# WaterMonitorV5_0.net
KiCad netlist of a schematic drawn in EAGLE
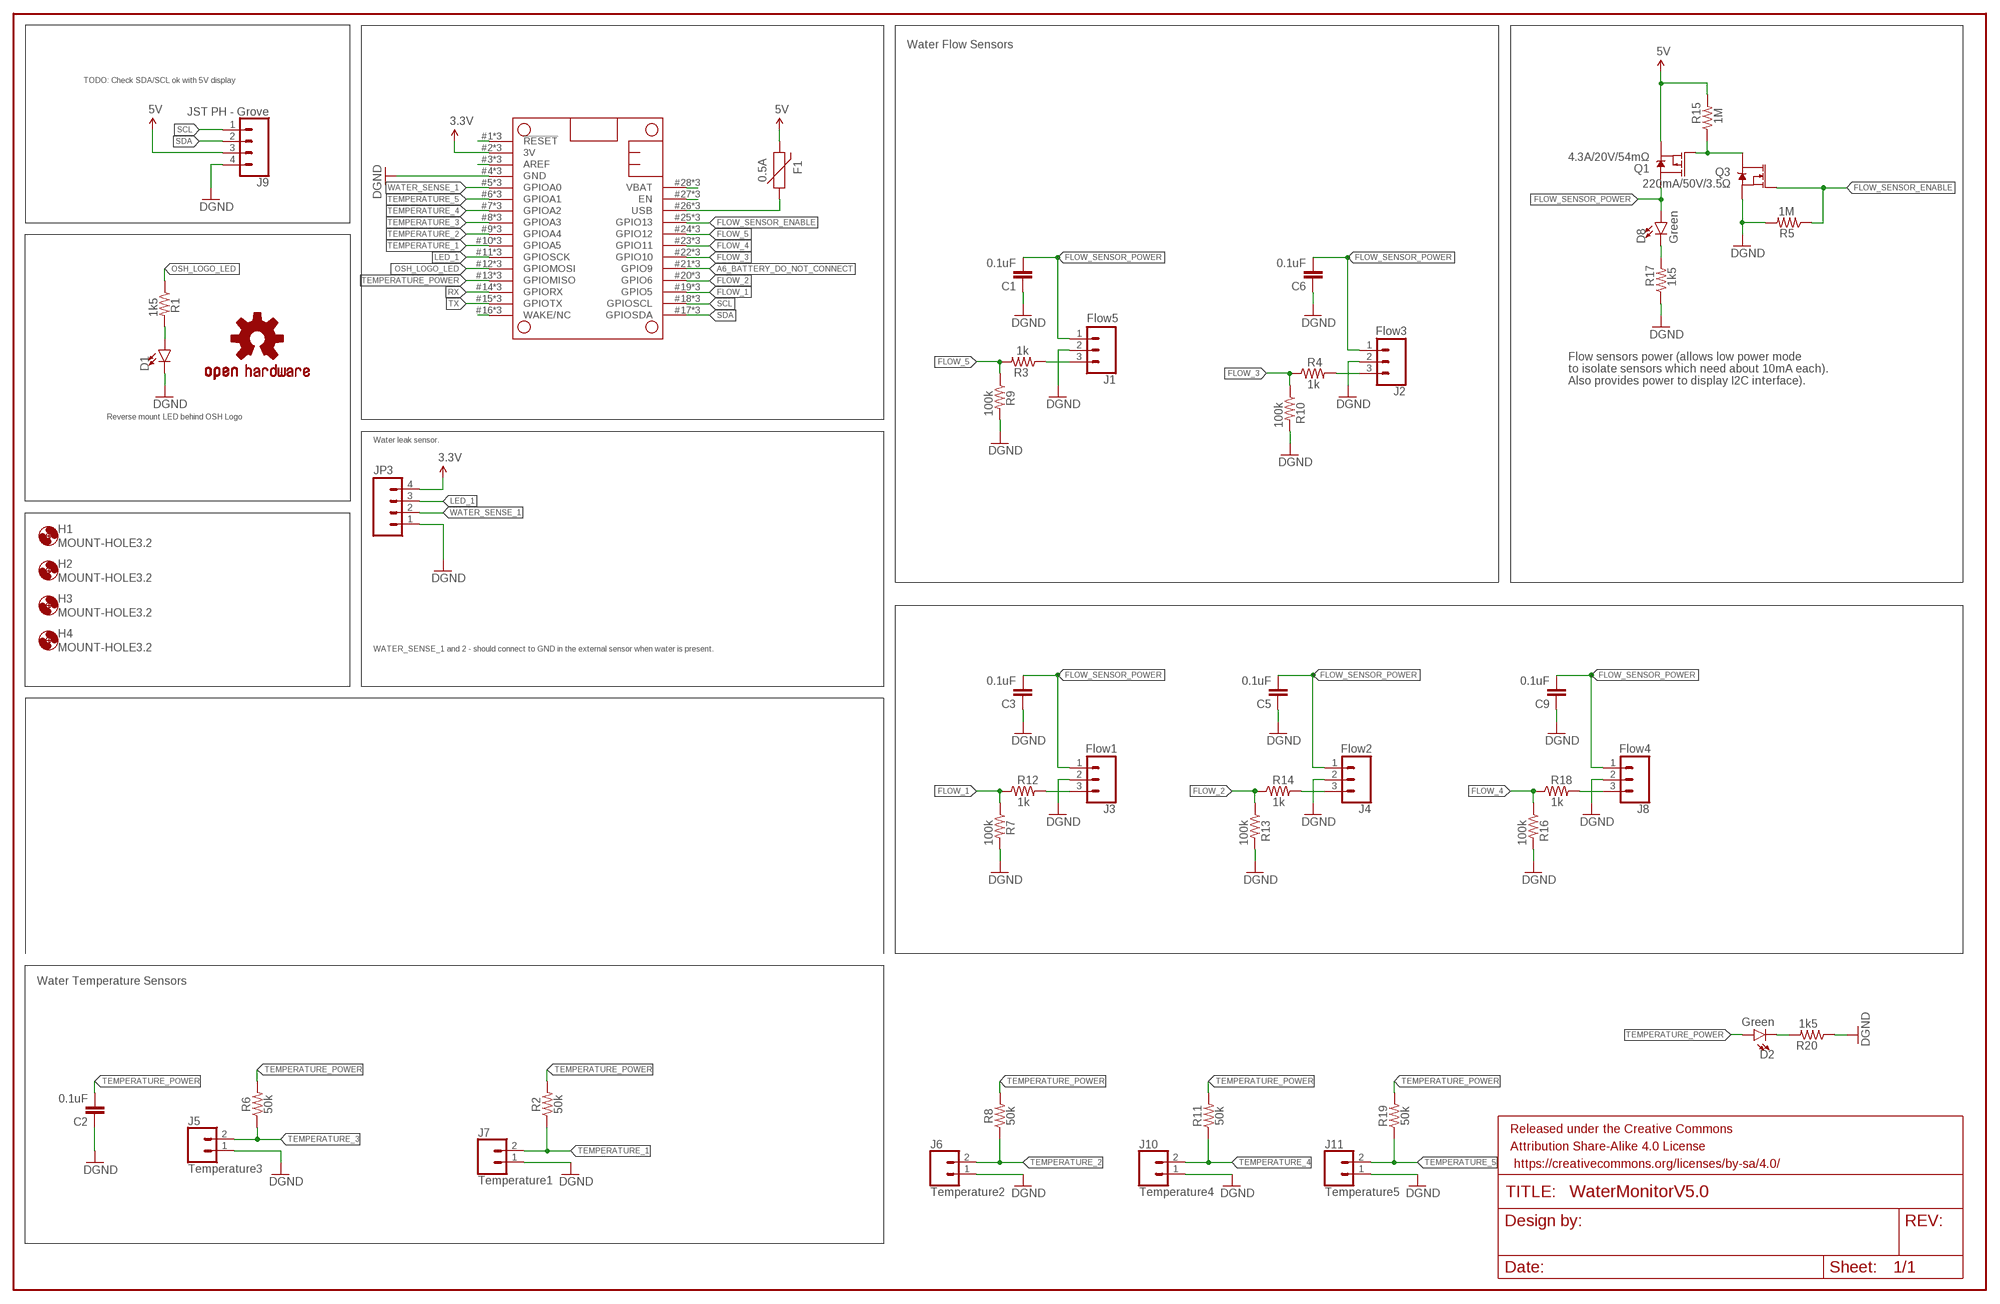
[diagram p0: schematic, sheet 1]

(export (version "E")
  (design (tool "Eeschema 10.0.6"))
  (components
    (comp (ref "C1")
      (value "0.1uF")
      (footprint "eagle-import:0805")
      (libsource (lib "eagle-import") (part "CAP0805"))
    )
    (comp (ref "C2")
      (value "0.1uF")
      (footprint "eagle-import:0805")
      (libsource (lib "eagle-import") (part "CAP0805"))
    )
    (comp (ref "C3")
      (value "0.1uF")
      (footprint "eagle-import:0805")
      (libsource (lib "eagle-import") (part "CAP0805"))
    )
    (comp (ref "C5")
      (value "0.1uF")
      (footprint "eagle-import:0805")
      (libsource (lib "eagle-import") (part "CAP0805"))
    )
    (comp (ref "C6")
      (value "0.1uF")
      (footprint "eagle-import:0805")
      (libsource (lib "eagle-import") (part "CAP0805"))
    )
    (comp (ref "C9")
      (value "0.1uF")
      (footprint "eagle-import:0805")
      (libsource (lib "eagle-import") (part "CAP0805"))
    )
    (comp (ref "D1")
      (value "LED1206-BOTTOM")
      (footprint "eagle-import:LED-1206-BOTTOM")
      (libsource (lib "eagle-import") (part "LED1206-BOTTOM"))
    )
    (comp (ref "D2")
      (value "Green")
      (footprint "eagle-import:LED-1206")
      (libsource (lib "eagle-import") (part "LED-BLUE1206"))
    )
    (comp (ref "D8")
      (value "Green")
      (footprint "eagle-import:LED-1206")
      (libsource (lib "eagle-import") (part "LED-BLUE1206"))
    )
    (comp (ref "F1")
      (value "0.5A")
      (footprint "eagle-import:1206")
      (libsource (lib "eagle-import") (part "PPTC_HALF-AMP"))
    )
    (comp (ref "FRAME2")
      (value "FRAME-LEDGER")
      (footprint "eagle-import:CREATIVE_COMMONS")
      (libsource (lib "eagle-import") (part "FRAME-LEDGER"))
    )
    (comp (ref "H1")
      (value "MOUNT-HOLE3.2")
      (footprint "eagle-import:3,2")
      (libsource (lib "eagle-import") (part "MOUNT-HOLE3.2"))
    )
    (comp (ref "H2")
      (value "MOUNT-HOLE3.2")
      (footprint "eagle-import:3,2")
      (libsource (lib "eagle-import") (part "MOUNT-HOLE3.2"))
    )
    (comp (ref "H3")
      (value "MOUNT-HOLE3.2")
      (footprint "eagle-import:3,2")
      (libsource (lib "eagle-import") (part "MOUNT-HOLE3.2"))
    )
    (comp (ref "H4")
      (value "MOUNT-HOLE3.2")
      (footprint "eagle-import:3,2")
      (libsource (lib "eagle-import") (part "MOUNT-HOLE3.2"))
    )
    (comp (ref "J1")
      (value "Flow5")
      (footprint "eagle-import:JST-HX-3-PTH-VERT")
      (libsource (lib "eagle-import") (part "CONN_03JST-HX-PTH-VERT"))
    )
    (comp (ref "J2")
      (value "Flow3")
      (footprint "eagle-import:JST-HX-3-PTH-VERT")
      (libsource (lib "eagle-import") (part "CONN_03JST-HX-PTH-VERT"))
    )
    (comp (ref "J3")
      (value "Flow1")
      (footprint "eagle-import:JST-HX-3-PTH-VERT")
      (libsource (lib "eagle-import") (part "CONN_03JST-HX-PTH-VERT"))
    )
    (comp (ref "J4")
      (value "Flow2")
      (footprint "eagle-import:JST-HX-3-PTH-VERT")
      (libsource (lib "eagle-import") (part "CONN_03JST-HX-PTH-VERT"))
    )
    (comp (ref "J5")
      (value "Temperature3")
      (footprint "eagle-import:MOLEX-1X2")
      (libsource (lib "eagle-import") (part "CONN_02POLAR"))
    )
    (comp (ref "J6")
      (value "Temperature2")
      (footprint "eagle-import:MOLEX-1X2")
      (libsource (lib "eagle-import") (part "CONN_02POLAR"))
    )
    (comp (ref "J7")
      (value "Temperature1")
      (footprint "eagle-import:MOLEX-1X2")
      (libsource (lib "eagle-import") (part "CONN_02POLAR"))
    )
    (comp (ref "J8")
      (value "Flow4")
      (footprint "eagle-import:JST-HX-3-PTH-VERT")
      (libsource (lib "eagle-import") (part "CONN_03JST-HX-PTH-VERT"))
    )
    (comp (ref "J9")
      (value "JST PH - Grove")
      (footprint "eagle-import:JST-4-PTH-VERT")
      (libsource (lib "eagle-import") (part "CONN_04JST-PTH-VERT"))
    )
    (comp (ref "J10")
      (value "Temperature4")
      (footprint "eagle-import:MOLEX-1X2")
      (libsource (lib "eagle-import") (part "CONN_02POLAR"))
    )
    (comp (ref "J11")
      (value "Temperature5")
      (footprint "eagle-import:MOLEX-1X2")
      (libsource (lib "eagle-import") (part "CONN_02POLAR"))
    )
    (comp (ref "JP3")
      (value "M04POLAR")
      (footprint "eagle-import:MOLEX-1X4@1")
      (libsource (lib "eagle-import") (part "M04POLAR"))
    )
    (comp (ref "LOGO1")
      (value "OSHW-LOGOM")
      (footprint "eagle-import:OSHW-LOGO-M")
      (libsource (lib "eagle-import") (part "OSHW-LOGOM"))
    )
    (comp (ref "MS1")
      (value "FEATHERWINGFEATHEWING_BREAKOUT")
      (footprint "eagle-import:FEATHERWING_BREAKOUT")
      (libsource (lib "eagle-import") (part "FEATHERWINGFEATHEWING_BREAKOUT"))
    )
    (comp (ref "Q1")
      (value "4.3A/20V/54mΩ")
      (footprint "eagle-import:SOT23-3")
      (libsource (lib "eagle-import") (part "MOSFET_PCH-IRLML2244"))
    )
    (comp (ref "Q3")
      (value "220mA/50V/3.5Ω")
      (footprint "eagle-import:SOT23-3")
      (libsource (lib "eagle-import") (part "MOSFET-NCH-BSS138"))
    )
    (comp (ref "R1")
      (value "1k5")
      (footprint "eagle-import:0805")
      (libsource (lib "eagle-import") (part "RESISTOR0805"))
    )
    (comp (ref "R2")
      (value "50k")
      (footprint "eagle-import:0805")
      (libsource (lib "eagle-import") (part "RESISTOR0805"))
    )
    (comp (ref "R3")
      (value "1k")
      (footprint "eagle-import:0805")
      (libsource (lib "eagle-import") (part "RESISTOR0805"))
    )
    (comp (ref "R4")
      (value "1k")
      (footprint "eagle-import:0805")
      (libsource (lib "eagle-import") (part "RESISTOR0805"))
    )
    (comp (ref "R5")
      (value "1M")
      (footprint "eagle-import:0805")
      (libsource (lib "eagle-import") (part "RESISTOR0805"))
    )
    (comp (ref "R6")
      (value "50k")
      (footprint "eagle-import:0805")
      (libsource (lib "eagle-import") (part "RESISTOR0805"))
    )
    (comp (ref "R7")
      (value "100k")
      (footprint "eagle-import:0805")
      (libsource (lib "eagle-import") (part "RESISTOR0805"))
    )
    (comp (ref "R8")
      (value "50k")
      (footprint "eagle-import:0805")
      (libsource (lib "eagle-import") (part "RESISTOR0805"))
    )
    (comp (ref "R9")
      (value "100k")
      (footprint "eagle-import:0805")
      (libsource (lib "eagle-import") (part "RESISTOR0805"))
    )
    (comp (ref "R10")
      (value "100k")
      (footprint "eagle-import:0805")
      (libsource (lib "eagle-import") (part "RESISTOR0805"))
    )
    (comp (ref "R11")
      (value "50k")
      (footprint "eagle-import:0805")
      (libsource (lib "eagle-import") (part "RESISTOR0805"))
    )
    (comp (ref "R12")
      (value "1k")
      (footprint "eagle-import:0805")
      (libsource (lib "eagle-import") (part "RESISTOR0805"))
    )
    (comp (ref "R13")
      (value "100k")
      (footprint "eagle-import:0805")
      (libsource (lib "eagle-import") (part "RESISTOR0805"))
    )
    (comp (ref "R14")
      (value "1k")
      (footprint "eagle-import:0805")
      (libsource (lib "eagle-import") (part "RESISTOR0805"))
    )
    (comp (ref "R15")
      (value "1M")
      (footprint "eagle-import:0805")
      (libsource (lib "eagle-import") (part "RESISTOR0805"))
    )
    (comp (ref "R16")
      (value "100k")
      (footprint "eagle-import:0805")
      (libsource (lib "eagle-import") (part "RESISTOR0805"))
    )
    (comp (ref "R17")
      (value "1k5")
      (footprint "eagle-import:0805")
      (libsource (lib "eagle-import") (part "RESISTOR0805"))
    )
    (comp (ref "R18")
      (value "1k")
      (footprint "eagle-import:0805")
      (libsource (lib "eagle-import") (part "RESISTOR0805"))
    )
    (comp (ref "R19")
      (value "50k")
      (footprint "eagle-import:0805")
      (libsource (lib "eagle-import") (part "RESISTOR0805"))
    )
    (comp (ref "R20")
      (value "1k5")
      (footprint "eagle-import:0805")
      (libsource (lib "eagle-import") (part "RESISTOR0805"))
    )
  )
  (nets
    (net (code "1") (name "3.3V") (class "Default")
      (node (ref "JP3") (pin "4") (pinfunction "4_4") (pintype "passive"))
      (node (ref "MS1") (pin "#2") (pinfunction "3V_#2") (pintype "power_in"))
      (node (ref "MS1") (pin "2") (pinfunction "3V_2") (pintype "power_in"))
      (node (ref "MS1") (pin "@2") (pinfunction "3V_@2") (pintype "power_in"))
    )
    (net (code "2") (name "5V") (class "Default")
      (node (ref "F1") (pin "2") (pinfunction "2_2") (pintype "bidirectional"))
      (node (ref "J9") (pin "3") (pinfunction "3_3") (pintype "passive"))
      (node (ref "Q1") (pin "2") (pinfunction "S_2") (pintype "bidirectional"))
      (node (ref "R15") (pin "2") (pinfunction "2_2") (pintype "passive"))
    )
    (net (code "3") (name "A6_BATTERY_DO_NOT_CONNECT") (class "Default")
      (node (ref "MS1") (pin "#21") (pinfunction "GPIO9_#21") (pintype "bidirectional"))
      (node (ref "MS1") (pin "21") (pinfunction "GPIO9_21") (pintype "bidirectional"))
      (node (ref "MS1") (pin "@21") (pinfunction "GPIO9_@21") (pintype "bidirectional"))
    )
    (net (code "4") (name "DGND") (class "Default")
      (node (ref "C1") (pin "1") (pinfunction "1_1") (pintype "passive"))
      (node (ref "C2") (pin "1") (pinfunction "1_1") (pintype "passive"))
      (node (ref "C3") (pin "1") (pinfunction "1_1") (pintype "passive"))
      (node (ref "C5") (pin "1") (pinfunction "1_1") (pintype "passive"))
      (node (ref "C6") (pin "1") (pinfunction "1_1") (pintype "passive"))
      (node (ref "C9") (pin "1") (pinfunction "1_1") (pintype "passive"))
      (node (ref "D1") (pin "C") (pinfunction "C_C") (pintype "passive"))
      (node (ref "J1") (pin "2") (pinfunction "2_2") (pintype "passive"))
      (node (ref "J10") (pin "1") (pinfunction "1_1") (pintype "passive"))
      (node (ref "J11") (pin "1") (pinfunction "1_1") (pintype "passive"))
      (node (ref "J2") (pin "2") (pinfunction "2_2") (pintype "passive"))
      (node (ref "J3") (pin "2") (pinfunction "2_2") (pintype "passive"))
      (node (ref "J4") (pin "2") (pinfunction "2_2") (pintype "passive"))
      (node (ref "J5") (pin "1") (pinfunction "1_1") (pintype "passive"))
      (node (ref "J6") (pin "1") (pinfunction "1_1") (pintype "passive"))
      (node (ref "J7") (pin "1") (pinfunction "1_1") (pintype "passive"))
      (node (ref "J8") (pin "2") (pinfunction "2_2") (pintype "passive"))
      (node (ref "J9") (pin "4") (pinfunction "4_4") (pintype "passive"))
      (node (ref "JP3") (pin "1") (pinfunction "1_1") (pintype "passive"))
      (node (ref "MS1") (pin "#4") (pinfunction "GND_#4") (pintype "power_in"))
      (node (ref "MS1") (pin "4") (pinfunction "GND_4") (pintype "power_in"))
      (node (ref "MS1") (pin "@4") (pinfunction "GND_@4") (pintype "power_in"))
      (node (ref "Q3") (pin "2") (pinfunction "S_2") (pintype "bidirectional"))
      (node (ref "R10") (pin "2") (pinfunction "2_2") (pintype "passive"))
      (node (ref "R13") (pin "2") (pinfunction "2_2") (pintype "passive"))
      (node (ref "R16") (pin "2") (pinfunction "2_2") (pintype "passive"))
      (node (ref "R17") (pin "1") (pinfunction "1_1") (pintype "passive"))
      (node (ref "R20") (pin "1") (pinfunction "1_1") (pintype "passive"))
      (node (ref "R5") (pin "2") (pinfunction "2_2") (pintype "passive"))
      (node (ref "R7") (pin "2") (pinfunction "2_2") (pintype "passive"))
      (node (ref "R9") (pin "2") (pinfunction "2_2") (pintype "passive"))
    )
    (net (code "5") (name "FLOW_1") (class "Default")
      (node (ref "MS1") (pin "#19") (pinfunction "GPIO5_#19") (pintype "bidirectional"))
      (node (ref "MS1") (pin "19") (pinfunction "GPIO5_19") (pintype "bidirectional"))
      (node (ref "MS1") (pin "@19") (pinfunction "GPIO5_@19") (pintype "bidirectional"))
      (node (ref "R12") (pin "1") (pinfunction "1_1") (pintype "passive"))
      (node (ref "R7") (pin "1") (pinfunction "1_1") (pintype "passive"))
    )
    (net (code "6") (name "FLOW_2") (class "Default")
      (node (ref "MS1") (pin "#20") (pinfunction "GPIO6_#20") (pintype "bidirectional"))
      (node (ref "MS1") (pin "20") (pinfunction "GPIO6_20") (pintype "bidirectional"))
      (node (ref "MS1") (pin "@20") (pinfunction "GPIO6_@20") (pintype "bidirectional"))
      (node (ref "R13") (pin "1") (pinfunction "1_1") (pintype "passive"))
      (node (ref "R14") (pin "1") (pinfunction "1_1") (pintype "passive"))
    )
    (net (code "7") (name "FLOW_3") (class "Default")
      (node (ref "MS1") (pin "#22") (pinfunction "GPIO10_#22") (pintype "bidirectional"))
      (node (ref "MS1") (pin "22") (pinfunction "GPIO10_22") (pintype "bidirectional"))
      (node (ref "MS1") (pin "@22") (pinfunction "GPIO10_@22") (pintype "bidirectional"))
      (node (ref "R10") (pin "1") (pinfunction "1_1") (pintype "passive"))
      (node (ref "R4") (pin "1") (pinfunction "1_1") (pintype "passive"))
    )
    (net (code "8") (name "FLOW_4") (class "Default")
      (node (ref "MS1") (pin "#23") (pinfunction "GPIO11_#23") (pintype "bidirectional"))
      (node (ref "MS1") (pin "23") (pinfunction "GPIO11_23") (pintype "bidirectional"))
      (node (ref "MS1") (pin "@23") (pinfunction "GPIO11_@23") (pintype "bidirectional"))
      (node (ref "R16") (pin "1") (pinfunction "1_1") (pintype "passive"))
      (node (ref "R18") (pin "1") (pinfunction "1_1") (pintype "passive"))
    )
    (net (code "9") (name "FLOW_5") (class "Default")
      (node (ref "MS1") (pin "#24") (pinfunction "GPIO12_#24") (pintype "bidirectional"))
      (node (ref "MS1") (pin "24") (pinfunction "GPIO12_24") (pintype "bidirectional"))
      (node (ref "MS1") (pin "@24") (pinfunction "GPIO12_@24") (pintype "bidirectional"))
      (node (ref "R3") (pin "2") (pinfunction "2_2") (pintype "passive"))
      (node (ref "R9") (pin "1") (pinfunction "1_1") (pintype "passive"))
    )
    (net (code "10") (name "FLOW_SENSOR_ENABLE") (class "Default")
      (node (ref "MS1") (pin "#25") (pinfunction "GPIO13_#25") (pintype "bidirectional"))
      (node (ref "MS1") (pin "25") (pinfunction "GPIO13_25") (pintype "bidirectional"))
      (node (ref "MS1") (pin "@25") (pinfunction "GPIO13_@25") (pintype "bidirectional"))
      (node (ref "Q3") (pin "1") (pinfunction "G_1") (pintype "bidirectional"))
      (node (ref "R5") (pin "1") (pinfunction "1_1") (pintype "passive"))
    )
    (net (code "11") (name "FLOW_SENSOR_POWER") (class "Default")
      (node (ref "C1") (pin "2") (pinfunction "2_2") (pintype "passive"))
      (node (ref "C3") (pin "2") (pinfunction "2_2") (pintype "passive"))
      (node (ref "C5") (pin "2") (pinfunction "2_2") (pintype "passive"))
      (node (ref "C6") (pin "2") (pinfunction "2_2") (pintype "passive"))
      (node (ref "C9") (pin "2") (pinfunction "2_2") (pintype "passive"))
      (node (ref "D8") (pin "A") (pinfunction "A_A") (pintype "passive"))
      (node (ref "J1") (pin "1") (pinfunction "1_1") (pintype "passive"))
      (node (ref "J2") (pin "1") (pinfunction "1_1") (pintype "passive"))
      (node (ref "J3") (pin "1") (pinfunction "1_1") (pintype "passive"))
      (node (ref "J4") (pin "1") (pinfunction "1_1") (pintype "passive"))
      (node (ref "J8") (pin "1") (pinfunction "1_1") (pintype "passive"))
      (node (ref "Q1") (pin "3") (pinfunction "D_3") (pintype "bidirectional"))
    )
    (net (code "12") (name "LED_1") (class "Default")
      (node (ref "JP3") (pin "3") (pinfunction "3_3") (pintype "passive"))
      (node (ref "MS1") (pin "#11") (pinfunction "GPIOSCK_#11") (pintype "bidirectional"))
      (node (ref "MS1") (pin "11") (pinfunction "GPIOSCK_11") (pintype "bidirectional"))
      (node (ref "MS1") (pin "@11") (pinfunction "GPIOSCK_@11") (pintype "bidirectional"))
    )
    (net (code "13") (name "Net-(D1-PadA)") (class "Default")
      (node (ref "D1") (pin "A") (pinfunction "A_A") (pintype "passive"))
      (node (ref "R1") (pin "2") (pinfunction "2_2") (pintype "passive"))
    )
    (net (code "14") (name "Net-(D2-PadC)") (class "Default")
      (node (ref "D2") (pin "C") (pinfunction "C_C") (pintype "passive"))
      (node (ref "R20") (pin "2") (pinfunction "2_2") (pintype "passive"))
    )
    (net (code "15") (name "Net-(D8-PadC)") (class "Default")
      (node (ref "D8") (pin "C") (pinfunction "C_C") (pintype "passive"))
      (node (ref "R17") (pin "2") (pinfunction "2_2") (pintype "passive"))
    )
    (net (code "16") (name "Net-(F1-Pad1)") (class "Default")
      (node (ref "F1") (pin "1") (pinfunction "1_1") (pintype "bidirectional"))
      (node (ref "MS1") (pin "#26") (pinfunction "USB_#26") (pintype "power_in"))
      (node (ref "MS1") (pin "26") (pinfunction "USB_26") (pintype "power_in"))
      (node (ref "MS1") (pin "@26") (pinfunction "USB_@26") (pintype "power_in"))
    )
    (net (code "17") (name "Net-(J1-Pad3)") (class "Default")
      (node (ref "J1") (pin "3") (pinfunction "3_3") (pintype "passive"))
      (node (ref "R3") (pin "1") (pinfunction "1_1") (pintype "passive"))
    )
    (net (code "18") (name "Net-(J2-Pad3)") (class "Default")
      (node (ref "J2") (pin "3") (pinfunction "3_3") (pintype "passive"))
      (node (ref "R4") (pin "2") (pinfunction "2_2") (pintype "passive"))
    )
    (net (code "19") (name "Net-(J3-Pad3)") (class "Default")
      (node (ref "J3") (pin "3") (pinfunction "3_3") (pintype "passive"))
      (node (ref "R12") (pin "2") (pinfunction "2_2") (pintype "passive"))
    )
    (net (code "20") (name "Net-(J4-Pad3)") (class "Default")
      (node (ref "J4") (pin "3") (pinfunction "3_3") (pintype "passive"))
      (node (ref "R14") (pin "2") (pinfunction "2_2") (pintype "passive"))
    )
    (net (code "21") (name "Net-(J8-Pad3)") (class "Default")
      (node (ref "J8") (pin "3") (pinfunction "3_3") (pintype "passive"))
      (node (ref "R18") (pin "2") (pinfunction "2_2") (pintype "passive"))
    )
    (net (code "22") (name "Net-(MS1-AREF-Pad#3)") (class "Default")
      (node (ref "MS1") (pin "#3") (pinfunction "AREF_#3") (pintype "passive"))
      (node (ref "MS1") (pin "3") (pinfunction "AREF_3") (pintype "passive"))
      (node (ref "MS1") (pin "@3") (pinfunction "AREF_@3") (pintype "passive"))
    )
    (net (code "23") (name "Net-(MS1-EN-Pad#27)") (class "Default")
      (node (ref "MS1") (pin "#27") (pinfunction "EN_#27") (pintype "passive"))
      (node (ref "MS1") (pin "27") (pinfunction "EN_27") (pintype "passive"))
      (node (ref "MS1") (pin "@27") (pinfunction "EN_@27") (pintype "passive"))
    )
    (net (code "24") (name "Net-(MS1-VBAT-Pad#28)") (class "Default")
      (node (ref "MS1") (pin "#28") (pinfunction "VBAT_#28") (pintype "power_in"))
      (node (ref "MS1") (pin "28") (pinfunction "VBAT_28") (pintype "power_in"))
      (node (ref "MS1") (pin "@28") (pinfunction "VBAT_@28") (pintype "power_in"))
    )
    (net (code "25") (name "Net-(MS1-WAKE{slash}NC-Pad#16)") (class "Default")
      (node (ref "MS1") (pin "#16") (pinfunction "WAKE/NC_#16") (pintype "passive"))
      (node (ref "MS1") (pin "16") (pinfunction "WAKE/NC_16") (pintype "passive"))
      (node (ref "MS1") (pin "@16") (pinfunction "WAKE/NC_@16") (pintype "passive"))
    )
    (net (code "26") (name "Net-(MS1-~{RESET}-Pad#1)") (class "Default")
      (node (ref "MS1") (pin "#1") (pinfunction "~{RESET}_#1") (pintype "input"))
      (node (ref "MS1") (pin "1") (pinfunction "~{RESET}_1") (pintype "input"))
      (node (ref "MS1") (pin "@1") (pinfunction "~{RESET}_@1") (pintype "input"))
    )
    (net (code "27") (name "Net-(Q1-G)") (class "Default")
      (node (ref "Q1") (pin "1") (pinfunction "G_1") (pintype "bidirectional"))
      (node (ref "Q3") (pin "3") (pinfunction "D_3") (pintype "bidirectional"))
      (node (ref "R15") (pin "1") (pinfunction "1_1") (pintype "passive"))
    )
    (net (code "28") (name "OSH_LOGO_LED") (class "Default")
      (node (ref "MS1") (pin "#12") (pinfunction "GPIOMOSI_#12") (pintype "bidirectional"))
      (node (ref "MS1") (pin "12") (pinfunction "GPIOMOSI_12") (pintype "bidirectional"))
      (node (ref "MS1") (pin "@12") (pinfunction "GPIOMOSI_@12") (pintype "bidirectional"))
      (node (ref "R1") (pin "1") (pinfunction "1_1") (pintype "passive"))
    )
    (net (code "29") (name "RX") (class "Default")
      (node (ref "MS1") (pin "#14") (pinfunction "GPIORX_#14") (pintype "bidirectional"))
      (node (ref "MS1") (pin "14") (pinfunction "GPIORX_14") (pintype "bidirectional"))
      (node (ref "MS1") (pin "@14") (pinfunction "GPIORX_@14") (pintype "bidirectional"))
    )
    (net (code "30") (name "SCL") (class "Default")
      (node (ref "J9") (pin "1") (pinfunction "1_1") (pintype "passive"))
      (node (ref "MS1") (pin "#18") (pinfunction "GPIOSCL_#18") (pintype "bidirectional"))
      (node (ref "MS1") (pin "18") (pinfunction "GPIOSCL_18") (pintype "bidirectional"))
      (node (ref "MS1") (pin "@!8") (pinfunction "GPIOSCL_@!8") (pintype "bidirectional"))
    )
    (net (code "31") (name "SDA") (class "Default")
      (node (ref "J9") (pin "2") (pinfunction "2_2") (pintype "passive"))
      (node (ref "MS1") (pin "#17") (pinfunction "GPIOSDA_#17") (pintype "bidirectional"))
      (node (ref "MS1") (pin "17") (pinfunction "GPIOSDA_17") (pintype "bidirectional"))
      (node (ref "MS1") (pin "@17") (pinfunction "GPIOSDA_@17") (pintype "bidirectional"))
    )
    (net (code "32") (name "TEMPERATURE_1") (class "Default")
      (node (ref "J7") (pin "2") (pinfunction "2_2") (pintype "passive"))
      (node (ref "MS1") (pin "#10") (pinfunction "GPIOA5_#10") (pintype "bidirectional"))
      (node (ref "MS1") (pin "10") (pinfunction "GPIOA5_10") (pintype "bidirectional"))
      (node (ref "MS1") (pin "@10") (pinfunction "GPIOA5_@10") (pintype "bidirectional"))
      (node (ref "R2") (pin "1") (pinfunction "1_1") (pintype "passive"))
    )
    (net (code "33") (name "TEMPERATURE_2") (class "Default")
      (node (ref "J6") (pin "2") (pinfunction "2_2") (pintype "passive"))
      (node (ref "MS1") (pin "#9") (pinfunction "GPIOA4_#9") (pintype "bidirectional"))
      (node (ref "MS1") (pin "9") (pinfunction "GPIOA4_9") (pintype "bidirectional"))
      (node (ref "MS1") (pin "@9") (pinfunction "GPIOA4_@9") (pintype "bidirectional"))
      (node (ref "R8") (pin "1") (pinfunction "1_1") (pintype "passive"))
    )
    (net (code "34") (name "TEMPERATURE_3") (class "Default")
      (node (ref "J5") (pin "2") (pinfunction "2_2") (pintype "passive"))
      (node (ref "MS1") (pin "#8") (pinfunction "GPIOA3_#8") (pintype "bidirectional"))
      (node (ref "MS1") (pin "8") (pinfunction "GPIOA3_8") (pintype "bidirectional"))
      (node (ref "MS1") (pin "@8") (pinfunction "GPIOA3_@8") (pintype "bidirectional"))
      (node (ref "R6") (pin "1") (pinfunction "1_1") (pintype "passive"))
    )
    (net (code "35") (name "TEMPERATURE_4") (class "Default")
      (node (ref "J10") (pin "2") (pinfunction "2_2") (pintype "passive"))
      (node (ref "MS1") (pin "#7") (pinfunction "GPIOA2_#7") (pintype "bidirectional"))
      (node (ref "MS1") (pin "7") (pinfunction "GPIOA2_7") (pintype "bidirectional"))
      (node (ref "MS1") (pin "@7") (pinfunction "GPIOA2_@7") (pintype "bidirectional"))
      (node (ref "R11") (pin "1") (pinfunction "1_1") (pintype "passive"))
    )
    (net (code "36") (name "TEMPERATURE_5") (class "Default")
      (node (ref "J11") (pin "2") (pinfunction "2_2") (pintype "passive"))
      (node (ref "MS1") (pin "#6") (pinfunction "GPIOA1_#6") (pintype "bidirectional"))
      (node (ref "MS1") (pin "6") (pinfunction "GPIOA1_6") (pintype "bidirectional"))
      (node (ref "MS1") (pin "@6") (pinfunction "GPIOA1_@6") (pintype "bidirectional"))
      (node (ref "R19") (pin "1") (pinfunction "1_1") (pintype "passive"))
    )
    (net (code "37") (name "TEMPERATURE_POWER") (class "Default")
      (node (ref "C2") (pin "2") (pinfunction "2_2") (pintype "passive"))
      (node (ref "D2") (pin "A") (pinfunction "A_A") (pintype "passive"))
      (node (ref "MS1") (pin "#13") (pinfunction "GPIOMISO_#13") (pintype "bidirectional"))
      (node (ref "MS1") (pin "13") (pinfunction "GPIOMISO_13") (pintype "bidirectional"))
      (node (ref "MS1") (pin "@13") (pinfunction "GPIOMISO_@13") (pintype "bidirectional"))
      (node (ref "R11") (pin "2") (pinfunction "2_2") (pintype "passive"))
      (node (ref "R19") (pin "2") (pinfunction "2_2") (pintype "passive"))
      (node (ref "R2") (pin "2") (pinfunction "2_2") (pintype "passive"))
      (node (ref "R6") (pin "2") (pinfunction "2_2") (pintype "passive"))
      (node (ref "R8") (pin "2") (pinfunction "2_2") (pintype "passive"))
    )
    (net (code "38") (name "TX") (class "Default")
      (node (ref "MS1") (pin "#15") (pinfunction "GPIOTX_#15") (pintype "bidirectional"))
      (node (ref "MS1") (pin "15") (pinfunction "GPIOTX_15") (pintype "bidirectional"))
      (node (ref "MS1") (pin "@15") (pinfunction "GPIOTX_@15") (pintype "bidirectional"))
    )
    (net (code "39") (name "WATER_SENSE_1") (class "Default")
      (node (ref "JP3") (pin "2") (pinfunction "2_2") (pintype "passive"))
      (node (ref "MS1") (pin "#5") (pinfunction "GPIOA0_#5") (pintype "bidirectional"))
      (node (ref "MS1") (pin "5") (pinfunction "GPIOA0_5") (pintype "bidirectional"))
      (node (ref "MS1") (pin "@5") (pinfunction "GPIOA0_@5") (pintype "bidirectional"))
    )
  )
)
